# Balancing.net
KiCad netlist of a schematic drawn in Altium Designer
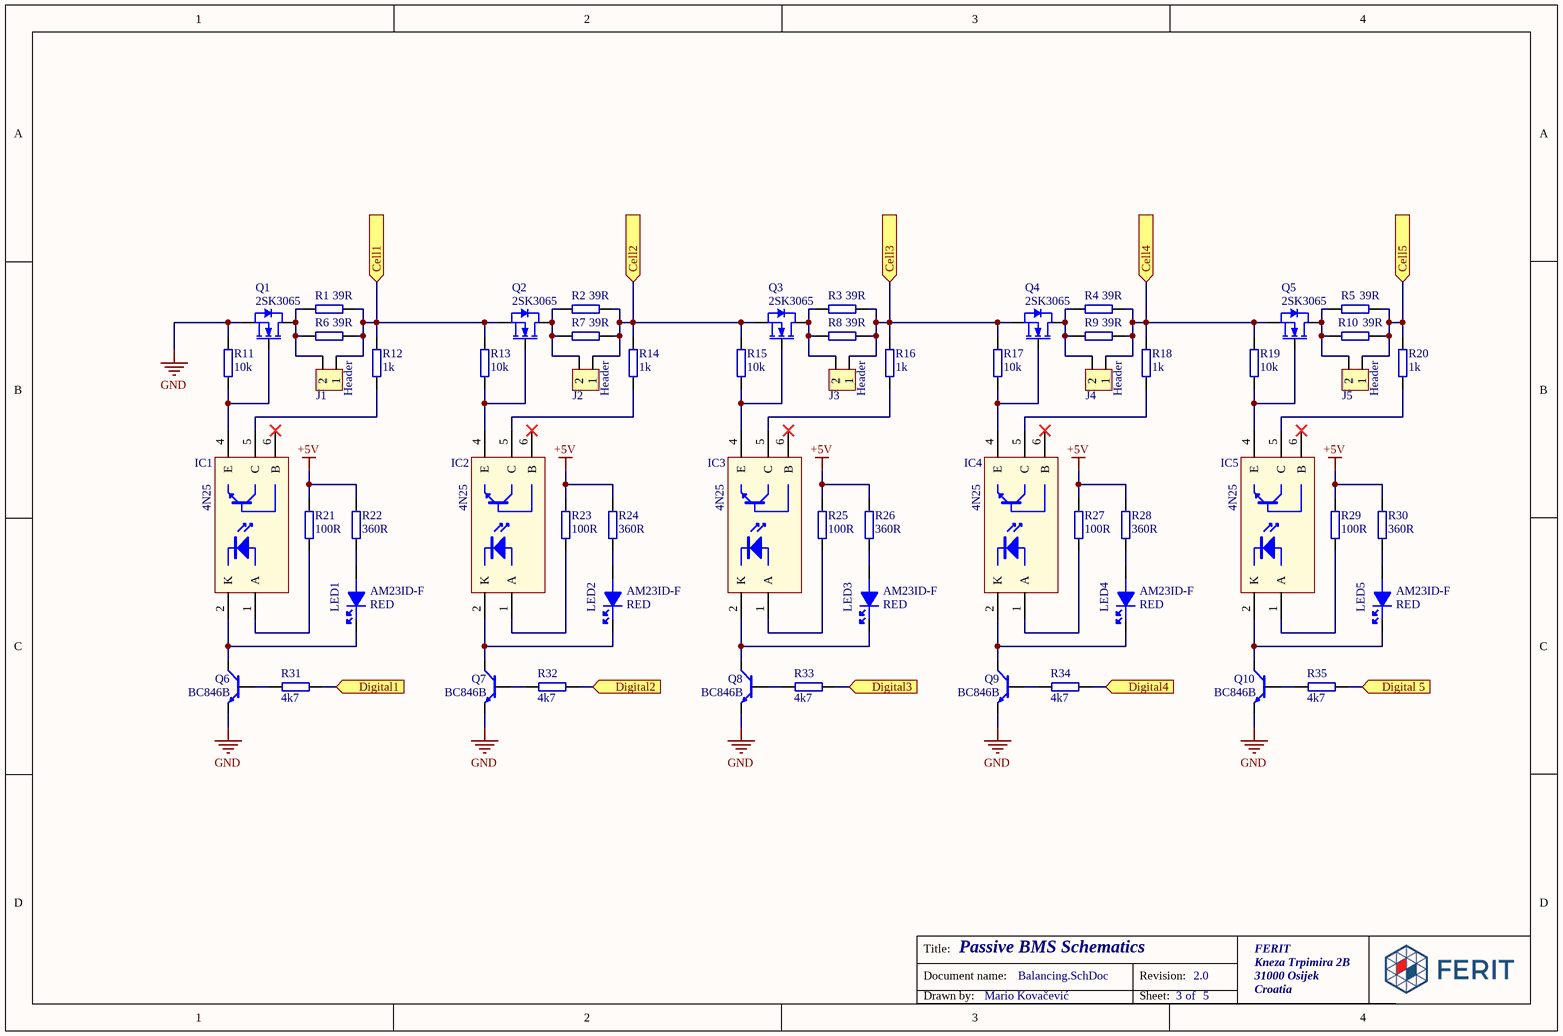
[diagram p0: Balancing.SchDoc]

(export (version "E")
  (design (tool "Eeschema 10.0.6"))
  (components
    (comp (ref "IC1")
      (value "4N25_DIP6")
      (footprint "DIP6")
      (description "Optocoupler [TH]")
      (fields
        (field (name "MANUFACTURER") "Vishay Semiconductors")
        (field (name "MANUFACTURER PART NUMBER") "4N25")
      )
      (libsource (lib "PassiveBMS_schlib") (part "4N25_DIP6"))
    )
    (comp (ref "IC2")
      (value "4N25_DIP6")
      (footprint "DIP6")
      (description "Optocoupler [TH]")
      (fields
        (field (name "MANUFACTURER") "Vishay Semiconductors")
        (field (name "MANUFACTURER PART NUMBER") "4N25")
      )
      (libsource (lib "PassiveBMS_schlib") (part "4N25_DIP6"))
    )
    (comp (ref "IC3")
      (value "4N25_DIP6")
      (footprint "DIP6")
      (description "Optocoupler [TH]")
      (fields
        (field (name "MANUFACTURER") "Vishay Semiconductors")
        (field (name "MANUFACTURER PART NUMBER") "4N25")
      )
      (libsource (lib "PassiveBMS_schlib") (part "4N25_DIP6"))
    )
    (comp (ref "IC4")
      (value "4N25_DIP6")
      (footprint "DIP6")
      (description "Optocoupler [TH]")
      (fields
        (field (name "MANUFACTURER") "Vishay Semiconductors")
        (field (name "MANUFACTURER PART NUMBER") "4N25")
      )
      (libsource (lib "PassiveBMS_schlib") (part "4N25_DIP6"))
    )
    (comp (ref "IC5")
      (value "4N25_DIP6")
      (footprint "DIP6")
      (description "Optocoupler [TH]")
      (fields
        (field (name "MANUFACTURER") "Vishay Semiconductors")
        (field (name "MANUFACTURER PART NUMBER") "4N25")
      )
      (libsource (lib "PassiveBMS_schlib") (part "4N25_DIP6"))
    )
    (comp (ref "J1")
      (value "2.54mm pitch")
      (footprint "HDR_1x2_2.54mm-MALE")
      (description "Header, 2-Pin [TH]")
      (fields
        (field (name "MANUFACTURER") "Molex")
        (field (name "MANUFACTURER PART NUMBER") "22-28-4150")
        (field (name "NAME") "Header")
        (field (name "PUBLISHER") "Altium Limited")
      )
      (libsource (lib "PassiveBMS_schlib") (part "Header 1x2"))
    )
    (comp (ref "J2")
      (value "2.54mm pitch")
      (footprint "HDR_1x2_2.54mm-MALE")
      (description "Header, 2-Pin [TH]")
      (fields
        (field (name "MANUFACTURER") "Molex")
        (field (name "MANUFACTURER PART NUMBER") "22-28-4150")
        (field (name "NAME") "Header")
        (field (name "PUBLISHER") "Altium Limited")
      )
      (libsource (lib "PassiveBMS_schlib") (part "Header 1x2"))
    )
    (comp (ref "J3")
      (value "2.54mm pitch")
      (footprint "HDR_1x2_2.54mm-MALE")
      (description "Header, 2-Pin [TH]")
      (fields
        (field (name "MANUFACTURER") "Molex")
        (field (name "MANUFACTURER PART NUMBER") "22-28-4150")
        (field (name "NAME") "Header")
        (field (name "PUBLISHER") "Altium Limited")
      )
      (libsource (lib "PassiveBMS_schlib") (part "Header 1x2"))
    )
    (comp (ref "J4")
      (value "2.54mm pitch")
      (footprint "HDR_1x2_2.54mm-MALE")
      (description "Header, 2-Pin [TH]")
      (fields
        (field (name "MANUFACTURER") "Molex")
        (field (name "MANUFACTURER PART NUMBER") "22-28-4150")
        (field (name "NAME") "Header")
        (field (name "PUBLISHER") "Altium Limited")
      )
      (libsource (lib "PassiveBMS_schlib") (part "Header 1x2"))
    )
    (comp (ref "J5")
      (value "2.54mm pitch")
      (footprint "HDR_1x2_2.54mm-MALE")
      (description "Header, 2-Pin [TH]")
      (fields
        (field (name "MANUFACTURER") "Molex")
        (field (name "MANUFACTURER PART NUMBER") "22-28-4150")
        (field (name "NAME") "Header")
        (field (name "PUBLISHER") "Altium Limited")
      )
      (libsource (lib "PassiveBMS_schlib") (part "Header 1x2"))
    )
    (comp (ref "LED1")
      (value "LED_SOT23")
      (footprint "LED_SOT23")
      (description "Red LED [SMD]")
      (fields
        (field (name "NAME") "RED")
        (field (name "MANUFACTURER") "Kingbright")
        (field (name "MANUFACTURER PART NUMBER") "AM23ID-F")
      )
      (libsource (lib "PassiveBMS_schlib") (part "LED_SOT23"))
    )
    (comp (ref "LED2")
      (value "LED_SOT23")
      (footprint "LED_SOT23")
      (description "Red LED [SMD]")
      (fields
        (field (name "NAME") "RED")
        (field (name "MANUFACTURER") "Kingbright")
        (field (name "MANUFACTURER PART NUMBER") "AM23ID-F")
      )
      (libsource (lib "PassiveBMS_schlib") (part "LED_SOT23"))
    )
    (comp (ref "LED3")
      (value "LED_SOT23")
      (footprint "LED_SOT23")
      (description "Red LED [SMD]")
      (fields
        (field (name "NAME") "RED")
        (field (name "MANUFACTURER") "Kingbright")
        (field (name "MANUFACTURER PART NUMBER") "AM23ID-F")
      )
      (libsource (lib "PassiveBMS_schlib") (part "LED_SOT23"))
    )
    (comp (ref "LED4")
      (value "LED_SOT23")
      (footprint "LED_SOT23")
      (description "Red LED [SMD]")
      (fields
        (field (name "NAME") "RED")
        (field (name "MANUFACTURER") "Kingbright")
        (field (name "MANUFACTURER PART NUMBER") "AM23ID-F")
      )
      (libsource (lib "PassiveBMS_schlib") (part "LED_SOT23"))
    )
    (comp (ref "LED5")
      (value "LED_SOT23")
      (footprint "LED_SOT23")
      (description "Red LED [SMD]")
      (fields
        (field (name "NAME") "RED")
        (field (name "MANUFACTURER") "Kingbright")
        (field (name "MANUFACTURER PART NUMBER") "AM23ID-F")
      )
      (libsource (lib "PassiveBMS_schlib") (part "LED_SOT23"))
    )
    (comp (ref "Q1")
      (value "2SK3065_SOT89")
      (footprint "N_MOSFET")
      (description "N Channel MOSFET [SMD]")
      (fields
        (field (name "MANUFACTURER_PART_NUMBER") "2SK3065T100")
        (field (name "NAME") "2SK3065")
        (field (name "MANUFACTURER") "Rohm")
        (field (name "COPYRIGHT") "Copyright (C) 2018 Accelerated Designs. All rights reserved")
      )
      (libsource (lib "PassiveBMS_schlib") (part "2SK3065_SOT89"))
    )
    (comp (ref "Q2")
      (value "2SK3065_SOT89")
      (footprint "N_MOSFET")
      (description "N Channel MOSFET [SMD]")
      (fields
        (field (name "MANUFACTURER_PART_NUMBER") "2SK3065T100")
        (field (name "NAME") "2SK3065")
        (field (name "MANUFACTURER") "Rohm")
        (field (name "COPYRIGHT") "Copyright (C) 2018 Accelerated Designs. All rights reserved")
      )
      (libsource (lib "PassiveBMS_schlib") (part "2SK3065_SOT89"))
    )
    (comp (ref "Q3")
      (value "2SK3065_SOT89")
      (footprint "N_MOSFET")
      (description "N Channel MOSFET [SMD]")
      (fields
        (field (name "MANUFACTURER_PART_NUMBER") "2SK3065T100")
        (field (name "NAME") "2SK3065")
        (field (name "MANUFACTURER") "Rohm")
        (field (name "COPYRIGHT") "Copyright (C) 2018 Accelerated Designs. All rights reserved")
      )
      (libsource (lib "PassiveBMS_schlib") (part "2SK3065_SOT89"))
    )
    (comp (ref "Q4")
      (value "2SK3065_SOT89")
      (footprint "N_MOSFET")
      (description "N Channel MOSFET [SMD]")
      (fields
        (field (name "MANUFACTURER_PART_NUMBER") "2SK3065T100")
        (field (name "NAME") "2SK3065")
        (field (name "MANUFACTURER") "Rohm")
        (field (name "COPYRIGHT") "Copyright (C) 2018 Accelerated Designs. All rights reserved")
      )
      (libsource (lib "PassiveBMS_schlib") (part "2SK3065_SOT89"))
    )
    (comp (ref "Q5")
      (value "2SK3065_SOT89")
      (footprint "N_MOSFET")
      (description "N Channel MOSFET [SMD]")
      (fields
        (field (name "MANUFACTURER_PART_NUMBER") "2SK3065T100")
        (field (name "NAME") "2SK3065")
        (field (name "MANUFACTURER") "Rohm")
        (field (name "COPYRIGHT") "Copyright (C) 2018 Accelerated Designs. All rights reserved")
      )
      (libsource (lib "PassiveBMS_schlib") (part "2SK3065_SOT89"))
    )
    (comp (ref "Q6")
      (value "BC846B_SOT23")
      (footprint "NPN_BJT_SOT23")
      (description "NPN transistor [SMD]")
      (fields
        (field (name "NAME") "BC846B")
        (field (name "MANUFACTURER PART NUMBER") "BC846ALT1G")
        (field (name "MANUFACTURER") "ON Semiconductor")
      )
      (libsource (lib "PassiveBMS_schlib") (part "BC846B_SOT23"))
    )
    (comp (ref "Q7")
      (value "BC846B_SOT23")
      (footprint "NPN_BJT_SOT23")
      (description "NPN transistor [SMD]")
      (fields
        (field (name "NAME") "BC846B")
        (field (name "MANUFACTURER PART NUMBER") "BC846ALT1G")
        (field (name "MANUFACTURER") "ON Semiconductor")
      )
      (libsource (lib "PassiveBMS_schlib") (part "BC846B_SOT23"))
    )
    (comp (ref "Q8")
      (value "BC846B_SOT23")
      (footprint "NPN_BJT_SOT23")
      (description "NPN transistor [SMD]")
      (fields
        (field (name "NAME") "BC846B")
        (field (name "MANUFACTURER PART NUMBER") "BC846ALT1G")
        (field (name "MANUFACTURER") "ON Semiconductor")
      )
      (libsource (lib "PassiveBMS_schlib") (part "BC846B_SOT23"))
    )
    (comp (ref "Q9")
      (value "BC846B_SOT23")
      (footprint "NPN_BJT_SOT23")
      (description "NPN transistor [SMD]")
      (fields
        (field (name "NAME") "BC846B")
        (field (name "MANUFACTURER PART NUMBER") "BC846ALT1G")
        (field (name "MANUFACTURER") "ON Semiconductor")
      )
      (libsource (lib "PassiveBMS_schlib") (part "BC846B_SOT23"))
    )
    (comp (ref "Q10")
      (value "BC846B_SOT23")
      (footprint "NPN_BJT_SOT23")
      (description "NPN transistor [SMD]")
      (fields
        (field (name "NAME") "BC846B")
        (field (name "MANUFACTURER PART NUMBER") "BC846ALT1G")
        (field (name "MANUFACTURER") "ON Semiconductor")
      )
      (libsource (lib "PassiveBMS_schlib") (part "BC846B_SOT23"))
    )
    (comp (ref "R1")
      (value "39R_2W")
      (footprint "R_2512")
      (description "Resistor [SMD]")
      (fields
        (field (name "NAME") "39R")
        (field (name "TOLERANCE") "1%")
        (field (name "MANUFACTURER") "TE Connectivity")
      )
      (libsource (lib "PassiveBMS_schlib") (part "R_39R_2512"))
    )
    (comp (ref "R2")
      (value "39R_2W")
      (footprint "R_2512")
      (description "Resistor [SMD]")
      (fields
        (field (name "NAME") "39R")
        (field (name "TOLERANCE") "1%")
        (field (name "MANUFACTURER") "TE Connectivity")
      )
      (libsource (lib "PassiveBMS_schlib") (part "R_39R_2512"))
    )
    (comp (ref "R3")
      (value "39R_2W")
      (footprint "R_2512")
      (description "Resistor [SMD]")
      (fields
        (field (name "NAME") "39R")
        (field (name "TOLERANCE") "1%")
        (field (name "MANUFACTURER") "TE Connectivity")
      )
      (libsource (lib "PassiveBMS_schlib") (part "R_39R_2512"))
    )
    (comp (ref "R4")
      (value "39R_2W")
      (footprint "R_2512")
      (description "Resistor [SMD]")
      (fields
        (field (name "NAME") "39R")
        (field (name "TOLERANCE") "1%")
        (field (name "MANUFACTURER") "TE Connectivity")
      )
      (libsource (lib "PassiveBMS_schlib") (part "R_39R_2512"))
    )
    (comp (ref "R5")
      (value "39R_2W")
      (footprint "R_2512")
      (description "Resistor [SMD]")
      (fields
        (field (name "NAME") "39R")
        (field (name "TOLERANCE") "1%")
        (field (name "MANUFACTURER") "TE Connectivity")
      )
      (libsource (lib "PassiveBMS_schlib") (part "R_39R_2512"))
    )
    (comp (ref "R6")
      (value "39R_2W")
      (footprint "R_2512")
      (description "Resistor [SMD]")
      (fields
        (field (name "NAME") "39R")
        (field (name "TOLERANCE") "1%")
        (field (name "MANUFACTURER") "TE Connectivity")
      )
      (libsource (lib "PassiveBMS_schlib") (part "R_39R_2512"))
    )
    (comp (ref "R7")
      (value "39R_2W")
      (footprint "R_2512")
      (description "Resistor [SMD]")
      (fields
        (field (name "NAME") "39R")
        (field (name "TOLERANCE") "1%")
        (field (name "MANUFACTURER") "TE Connectivity")
      )
      (libsource (lib "PassiveBMS_schlib") (part "R_39R_2512"))
    )
    (comp (ref "R8")
      (value "39R_2W")
      (footprint "R_2512")
      (description "Resistor [SMD]")
      (fields
        (field (name "NAME") "39R")
        (field (name "TOLERANCE") "1%")
        (field (name "MANUFACTURER") "TE Connectivity")
      )
      (libsource (lib "PassiveBMS_schlib") (part "R_39R_2512"))
    )
    (comp (ref "R9")
      (value "39R_2W")
      (footprint "R_2512")
      (description "Resistor [SMD]")
      (fields
        (field (name "NAME") "39R")
        (field (name "TOLERANCE") "1%")
        (field (name "MANUFACTURER") "TE Connectivity")
      )
      (libsource (lib "PassiveBMS_schlib") (part "R_39R_2512"))
    )
    (comp (ref "R10")
      (value "39R_2W")
      (footprint "R_2512")
      (description "Resistor [SMD]")
      (fields
        (field (name "NAME") "39R")
        (field (name "TOLERANCE") "1%")
        (field (name "MANUFACTURER") "TE Connectivity")
      )
      (libsource (lib "PassiveBMS_schlib") (part "R_39R_2512"))
    )
    (comp (ref "R11")
      (value "10k_125mW")
      (footprint "R_0805")
      (description "Resistor [SMD]")
      (fields
        (field (name "NAME") "10k")
        (field (name "TOLERANCE") "1%")
        (field (name "MANUFACTURER") "Vishay")
      )
      (libsource (lib "PassiveBMS_schlib") (part "R_10k_0805"))
    )
    (comp (ref "R12")
      (value "1k_125mW")
      (footprint "R_0805")
      (description "Resistor [SMD]")
      (fields
        (field (name "NAME") "1k")
        (field (name "TOLERANCE") "1%")
        (field (name "MANUFACTURER") "Vishay")
      )
      (libsource (lib "PassiveBMS_schlib") (part "R_1k_0805"))
    )
    (comp (ref "R13")
      (value "10k_125mW")
      (footprint "R_0805")
      (description "Resistor [SMD]")
      (fields
        (field (name "NAME") "10k")
        (field (name "TOLERANCE") "1%")
        (field (name "MANUFACTURER") "Vishay")
      )
      (libsource (lib "PassiveBMS_schlib") (part "R_10k_0805"))
    )
    (comp (ref "R14")
      (value "1k_125mW")
      (footprint "R_0805")
      (description "Resistor [SMD]")
      (fields
        (field (name "NAME") "1k")
        (field (name "TOLERANCE") "1%")
        (field (name "MANUFACTURER") "Vishay")
      )
      (libsource (lib "PassiveBMS_schlib") (part "R_1k_0805"))
    )
    (comp (ref "R15")
      (value "10k_125mW")
      (footprint "R_0805")
      (description "Resistor [SMD]")
      (fields
        (field (name "NAME") "10k")
        (field (name "TOLERANCE") "1%")
        (field (name "MANUFACTURER") "Vishay")
      )
      (libsource (lib "PassiveBMS_schlib") (part "R_10k_0805"))
    )
    (comp (ref "R16")
      (value "1k_125mW")
      (footprint "R_0805")
      (description "Resistor [SMD]")
      (fields
        (field (name "NAME") "1k")
        (field (name "TOLERANCE") "1%")
        (field (name "MANUFACTURER") "Vishay")
      )
      (libsource (lib "PassiveBMS_schlib") (part "R_1k_0805"))
    )
    (comp (ref "R17")
      (value "10k_125mW")
      (footprint "R_0805")
      (description "Resistor [SMD]")
      (fields
        (field (name "NAME") "10k")
        (field (name "TOLERANCE") "1%")
        (field (name "MANUFACTURER") "Vishay")
      )
      (libsource (lib "PassiveBMS_schlib") (part "R_10k_0805"))
    )
    (comp (ref "R18")
      (value "1k_125mW")
      (footprint "R_0805")
      (description "Resistor [SMD]")
      (fields
        (field (name "NAME") "1k")
        (field (name "TOLERANCE") "1%")
        (field (name "MANUFACTURER") "Vishay")
      )
      (libsource (lib "PassiveBMS_schlib") (part "R_1k_0805"))
    )
    (comp (ref "R19")
      (value "10k_125mW")
      (footprint "R_0805")
      (description "Resistor [SMD]")
      (fields
        (field (name "NAME") "10k")
        (field (name "TOLERANCE") "1%")
        (field (name "MANUFACTURER") "Vishay")
      )
      (libsource (lib "PassiveBMS_schlib") (part "R_10k_0805"))
    )
    (comp (ref "R20")
      (value "1k_125mW")
      (footprint "R_0805")
      (description "Resistor [SMD]")
      (fields
        (field (name "NAME") "1k")
        (field (name "TOLERANCE") "1%")
        (field (name "MANUFACTURER") "Vishay")
      )
      (libsource (lib "PassiveBMS_schlib") (part "R_1k_0805"))
    )
    (comp (ref "R21")
      (value "100R_500mW")
      (footprint "R_0805")
      (description "Resistor [SMD]")
      (fields
        (field (name "NAME") "100R")
        (field (name "TOLERANCE") "1%")
        (field (name "MANUFACTURER") "Vishay Dale")
      )
      (libsource (lib "PassiveBMS_schlib") (part "R_100R_0805"))
    )
    (comp (ref "R22")
      (value "360R_125mW")
      (footprint "R_0805")
      (description "Resistor [SMD]")
      (fields
        (field (name "NAME") "360R")
        (field (name "TOLERANCE") "1%")
        (field (name "MANUFACTURER") "Vishay")
      )
      (libsource (lib "PassiveBMS_schlib") (part "R_360R_0805"))
    )
    (comp (ref "R23")
      (value "100R_500mW")
      (footprint "R_0805")
      (description "Resistor [SMD]")
      (fields
        (field (name "NAME") "100R")
        (field (name "TOLERANCE") "1%")
        (field (name "MANUFACTURER") "Vishay Dale")
      )
      (libsource (lib "PassiveBMS_schlib") (part "R_100R_0805"))
    )
    (comp (ref "R24")
      (value "360R_125mW")
      (footprint "R_0805")
      (description "Resistor [SMD]")
      (fields
        (field (name "NAME") "360R")
        (field (name "TOLERANCE") "1%")
        (field (name "MANUFACTURER") "Vishay")
      )
      (libsource (lib "PassiveBMS_schlib") (part "R_360R_0805"))
    )
    (comp (ref "R25")
      (value "100R_500mW")
      (footprint "R_0805")
      (description "Resistor [SMD]")
      (fields
        (field (name "NAME") "100R")
        (field (name "TOLERANCE") "1%")
        (field (name "MANUFACTURER") "Vishay Dale")
      )
      (libsource (lib "PassiveBMS_schlib") (part "R_100R_0805"))
    )
    (comp (ref "R26")
      (value "360R_125mW")
      (footprint "R_0805")
      (description "Resistor [SMD]")
      (fields
        (field (name "NAME") "360R")
        (field (name "TOLERANCE") "1%")
        (field (name "MANUFACTURER") "Vishay")
      )
      (libsource (lib "PassiveBMS_schlib") (part "R_360R_0805"))
    )
    (comp (ref "R27")
      (value "100R_500mW")
      (footprint "R_0805")
      (description "Resistor [SMD]")
      (fields
        (field (name "NAME") "100R")
        (field (name "TOLERANCE") "1%")
        (field (name "MANUFACTURER") "Vishay Dale")
      )
      (libsource (lib "PassiveBMS_schlib") (part "R_100R_0805"))
    )
    (comp (ref "R28")
      (value "360R_125mW")
      (footprint "R_0805")
      (description "Resistor [SMD]")
      (fields
        (field (name "NAME") "360R")
        (field (name "TOLERANCE") "1%")
        (field (name "MANUFACTURER") "Vishay")
      )
      (libsource (lib "PassiveBMS_schlib") (part "R_360R_0805"))
    )
    (comp (ref "R29")
      (value "100R_500mW")
      (footprint "R_0805")
      (description "Resistor [SMD]")
      (fields
        (field (name "NAME") "100R")
        (field (name "TOLERANCE") "1%")
        (field (name "MANUFACTURER") "Vishay Dale")
      )
      (libsource (lib "PassiveBMS_schlib") (part "R_100R_0805"))
    )
    (comp (ref "R30")
      (value "360R_125mW")
      (footprint "R_0805")
      (description "Resistor [SMD]")
      (fields
        (field (name "NAME") "360R")
        (field (name "TOLERANCE") "1%")
        (field (name "MANUFACTURER") "Vishay")
      )
      (libsource (lib "PassiveBMS_schlib") (part "R_360R_0805"))
    )
    (comp (ref "R31")
      (value "4k7_125mW")
      (footprint "R_0805")
      (description "Resistor [SMD]")
      (fields
        (field (name "NAME") "4k7")
        (field (name "TOLERANCE") "1%")
        (field (name "MANUFACTURER") "Vishay")
      )
      (libsource (lib "PassiveBMS_schlib") (part "R_4k7_0805"))
    )
    (comp (ref "R32")
      (value "4k7_125mW")
      (footprint "R_0805")
      (description "Resistor [SMD]")
      (fields
        (field (name "NAME") "4k7")
        (field (name "TOLERANCE") "1%")
        (field (name "MANUFACTURER") "Vishay")
      )
      (libsource (lib "PassiveBMS_schlib") (part "R_4k7_0805"))
    )
    (comp (ref "R33")
      (value "4k7_125mW")
      (footprint "R_0805")
      (description "Resistor [SMD]")
      (fields
        (field (name "NAME") "4k7")
        (field (name "TOLERANCE") "1%")
        (field (name "MANUFACTURER") "Vishay")
      )
      (libsource (lib "PassiveBMS_schlib") (part "R_4k7_0805"))
    )
    (comp (ref "R34")
      (value "4k7_125mW")
      (footprint "R_0805")
      (description "Resistor [SMD]")
      (fields
        (field (name "NAME") "4k7")
        (field (name "TOLERANCE") "1%")
        (field (name "MANUFACTURER") "Vishay")
      )
      (libsource (lib "PassiveBMS_schlib") (part "R_4k7_0805"))
    )
    (comp (ref "R35")
      (value "4k7_125mW")
      (footprint "R_0805")
      (description "Resistor [SMD]")
      (fields
        (field (name "NAME") "4k7")
        (field (name "TOLERANCE") "1%")
        (field (name "MANUFACTURER") "Vishay")
      )
      (libsource (lib "PassiveBMS_schlib") (part "R_4k7_0805"))
    )
  )
  (nets
    (net (code "1") (name "+5V") (class "Default")
      (node (ref "R21") (pin "2") (pinfunction "2_2") (pintype "passive"))
      (node (ref "R22") (pin "1") (pinfunction "1_1") (pintype "passive"))
      (node (ref "R23") (pin "1") (pinfunction "1_1") (pintype "passive"))
      (node (ref "R24") (pin "1") (pinfunction "1_1") (pintype "passive"))
      (node (ref "R25") (pin "1") (pinfunction "1_1") (pintype "passive"))
      (node (ref "R26") (pin "1") (pinfunction "1_1") (pintype "passive"))
      (node (ref "R27") (pin "1") (pinfunction "1_1") (pintype "passive"))
      (node (ref "R28") (pin "1") (pinfunction "1_1") (pintype "passive"))
      (node (ref "R29") (pin "1") (pinfunction "1_1") (pintype "passive"))
      (node (ref "R30") (pin "1") (pinfunction "1_1") (pintype "passive"))
    )
    (net (code "2") (name "/Cell1") (class "Default")
      (node (ref "J1") (pin "1") (pinfunction "1_1") (pintype "passive"))
      (node (ref "Q2") (pin "3") (pinfunction "S_3") (pintype "passive"))
      (node (ref "R1") (pin "1") (pinfunction "1_1") (pintype "passive"))
      (node (ref "R12") (pin "1") (pinfunction "1_1") (pintype "passive"))
      (node (ref "R13") (pin "1") (pinfunction "1_1") (pintype "passive"))
      (node (ref "R6") (pin "1") (pinfunction "1_1") (pintype "passive"))
    )
    (net (code "3") (name "/Cell2") (class "Default")
      (node (ref "J2") (pin "1") (pinfunction "1_1") (pintype "passive"))
      (node (ref "Q3") (pin "3") (pinfunction "S_3") (pintype "passive"))
      (node (ref "R14") (pin "1") (pinfunction "1_1") (pintype "passive"))
      (node (ref "R15") (pin "1") (pinfunction "1_1") (pintype "passive"))
      (node (ref "R2") (pin "1") (pinfunction "1_1") (pintype "passive"))
      (node (ref "R7") (pin "1") (pinfunction "1_1") (pintype "passive"))
    )
    (net (code "4") (name "/Cell3") (class "Default")
      (node (ref "J3") (pin "1") (pinfunction "1_1") (pintype "passive"))
      (node (ref "Q4") (pin "3") (pinfunction "S_3") (pintype "passive"))
      (node (ref "R16") (pin "1") (pinfunction "1_1") (pintype "passive"))
      (node (ref "R17") (pin "1") (pinfunction "1_1") (pintype "passive"))
      (node (ref "R3") (pin "1") (pinfunction "1_1") (pintype "passive"))
      (node (ref "R8") (pin "1") (pinfunction "1_1") (pintype "passive"))
    )
    (net (code "5") (name "/Cell4") (class "Default")
      (node (ref "J4") (pin "1") (pinfunction "1_1") (pintype "passive"))
      (node (ref "Q5") (pin "3") (pinfunction "S_3") (pintype "passive"))
      (node (ref "R18") (pin "1") (pinfunction "1_1") (pintype "passive"))
      (node (ref "R19") (pin "1") (pinfunction "1_1") (pintype "passive"))
      (node (ref "R4") (pin "1") (pinfunction "1_1") (pintype "passive"))
      (node (ref "R9") (pin "1") (pinfunction "1_1") (pintype "passive"))
    )
    (net (code "6") (name "/Cell5") (class "Default")
      (node (ref "J5") (pin "1") (pinfunction "1_1") (pintype "passive"))
      (node (ref "R10") (pin "1") (pinfunction "1_1") (pintype "passive"))
      (node (ref "R20") (pin "1") (pinfunction "1_1") (pintype "passive"))
      (node (ref "R5") (pin "1") (pinfunction "1_1") (pintype "passive"))
    )
    (net (code "7") (name "/Digital 5") (class "Default")
      (node (ref "R35") (pin "2") (pinfunction "2_2") (pintype "passive"))
    )
    (net (code "8") (name "/Digital1") (class "Default")
      (node (ref "R31") (pin "1") (pinfunction "1_1") (pintype "passive"))
    )
    (net (code "9") (name "/Digital2") (class "Default")
      (node (ref "R32") (pin "1") (pinfunction "1_1") (pintype "passive"))
    )
    (net (code "10") (name "/Digital3") (class "Default")
      (node (ref "R33") (pin "2") (pinfunction "2_2") (pintype "passive"))
    )
    (net (code "11") (name "/Digital4") (class "Default")
      (node (ref "R34") (pin "1") (pinfunction "1_1") (pintype "passive"))
    )
    (net (code "12") (name "GND") (class "Default")
      (node (ref "Q1") (pin "3") (pinfunction "S_3") (pintype "passive"))
      (node (ref "Q10") (pin "3") (pinfunction "E_3") (pintype "passive"))
      (node (ref "Q6") (pin "3") (pinfunction "E_3") (pintype "passive"))
      (node (ref "Q7") (pin "3") (pinfunction "E_3") (pintype "passive"))
      (node (ref "Q8") (pin "3") (pinfunction "E_3") (pintype "passive"))
      (node (ref "Q9") (pin "3") (pinfunction "E_3") (pintype "passive"))
      (node (ref "R11") (pin "1") (pinfunction "1_1") (pintype "passive"))
    )
    (net (code "13") (name "Net-(IC1-A)") (class "Default")
      (node (ref "IC1") (pin "1") (pinfunction "A_1") (pintype "passive"))
      (node (ref "R21") (pin "1") (pinfunction "1_1") (pintype "passive"))
    )
    (net (code "14") (name "Net-(IC1-C)") (class "Default")
      (node (ref "IC1") (pin "5") (pinfunction "C_5") (pintype "passive"))
      (node (ref "R12") (pin "2") (pinfunction "2_2") (pintype "passive"))
    )
    (net (code "15") (name "Net-(IC1-E)") (class "Default")
      (node (ref "IC1") (pin "4") (pinfunction "E_4") (pintype "passive"))
      (node (ref "Q1") (pin "1") (pinfunction "G_1") (pintype "passive"))
      (node (ref "R11") (pin "2") (pinfunction "2_2") (pintype "passive"))
    )
    (net (code "16") (name "Net-(IC1-K)") (class "Default")
      (node (ref "IC1") (pin "2") (pinfunction "K_2") (pintype "passive"))
      (node (ref "LED1") (pin "3") (pinfunction "K_3") (pintype "passive"))
      (node (ref "Q6") (pin "1") (pinfunction "C_1") (pintype "passive"))
    )
    (net (code "17") (name "Net-(IC2-A)") (class "Default")
      (node (ref "IC2") (pin "1") (pinfunction "A_1") (pintype "passive"))
      (node (ref "R23") (pin "2") (pinfunction "2_2") (pintype "passive"))
    )
    (net (code "18") (name "Net-(IC2-C)") (class "Default")
      (node (ref "IC2") (pin "5") (pinfunction "C_5") (pintype "passive"))
      (node (ref "R14") (pin "2") (pinfunction "2_2") (pintype "passive"))
    )
    (net (code "19") (name "Net-(IC2-E)") (class "Default")
      (node (ref "IC2") (pin "4") (pinfunction "E_4") (pintype "passive"))
      (node (ref "Q2") (pin "1") (pinfunction "G_1") (pintype "passive"))
      (node (ref "R13") (pin "2") (pinfunction "2_2") (pintype "passive"))
    )
    (net (code "20") (name "Net-(IC2-K)") (class "Default")
      (node (ref "IC2") (pin "2") (pinfunction "K_2") (pintype "passive"))
      (node (ref "LED2") (pin "3") (pinfunction "K_3") (pintype "passive"))
      (node (ref "Q7") (pin "1") (pinfunction "C_1") (pintype "passive"))
    )
    (net (code "21") (name "Net-(IC3-A)") (class "Default")
      (node (ref "IC3") (pin "1") (pinfunction "A_1") (pintype "passive"))
      (node (ref "R25") (pin "2") (pinfunction "2_2") (pintype "passive"))
    )
    (net (code "22") (name "Net-(IC3-C)") (class "Default")
      (node (ref "IC3") (pin "5") (pinfunction "C_5") (pintype "passive"))
      (node (ref "R16") (pin "2") (pinfunction "2_2") (pintype "passive"))
    )
    (net (code "23") (name "Net-(IC3-E)") (class "Default")
      (node (ref "IC3") (pin "4") (pinfunction "E_4") (pintype "passive"))
      (node (ref "Q3") (pin "1") (pinfunction "G_1") (pintype "passive"))
      (node (ref "R15") (pin "2") (pinfunction "2_2") (pintype "passive"))
    )
    (net (code "24") (name "Net-(IC3-K)") (class "Default")
      (node (ref "IC3") (pin "2") (pinfunction "K_2") (pintype "passive"))
      (node (ref "LED3") (pin "3") (pinfunction "K_3") (pintype "passive"))
      (node (ref "Q8") (pin "1") (pinfunction "C_1") (pintype "passive"))
    )
    (net (code "25") (name "Net-(IC4-A)") (class "Default")
      (node (ref "IC4") (pin "1") (pinfunction "A_1") (pintype "passive"))
      (node (ref "R27") (pin "2") (pinfunction "2_2") (pintype "passive"))
    )
    (net (code "26") (name "Net-(IC4-C)") (class "Default")
      (node (ref "IC4") (pin "5") (pinfunction "C_5") (pintype "passive"))
      (node (ref "R18") (pin "2") (pinfunction "2_2") (pintype "passive"))
    )
    (net (code "27") (name "Net-(IC4-E)") (class "Default")
      (node (ref "IC4") (pin "4") (pinfunction "E_4") (pintype "passive"))
      (node (ref "Q4") (pin "1") (pinfunction "G_1") (pintype "passive"))
      (node (ref "R17") (pin "2") (pinfunction "2_2") (pintype "passive"))
    )
    (net (code "28") (name "Net-(IC4-K)") (class "Default")
      (node (ref "IC4") (pin "2") (pinfunction "K_2") (pintype "passive"))
      (node (ref "LED4") (pin "3") (pinfunction "K_3") (pintype "passive"))
      (node (ref "Q9") (pin "1") (pinfunction "C_1") (pintype "passive"))
    )
    (net (code "29") (name "Net-(IC5-A)") (class "Default")
      (node (ref "IC5") (pin "1") (pinfunction "A_1") (pintype "passive"))
      (node (ref "R29") (pin "2") (pinfunction "2_2") (pintype "passive"))
    )
    (net (code "30") (name "Net-(IC5-C)") (class "Default")
      (node (ref "IC5") (pin "5") (pinfunction "C_5") (pintype "passive"))
      (node (ref "R20") (pin "2") (pinfunction "2_2") (pintype "passive"))
    )
    (net (code "31") (name "Net-(IC5-E)") (class "Default")
      (node (ref "IC5") (pin "4") (pinfunction "E_4") (pintype "passive"))
      (node (ref "Q5") (pin "1") (pinfunction "G_1") (pintype "passive"))
      (node (ref "R19") (pin "2") (pinfunction "2_2") (pintype "passive"))
    )
    (net (code "32") (name "Net-(IC5-K)") (class "Default")
      (node (ref "IC5") (pin "2") (pinfunction "K_2") (pintype "passive"))
      (node (ref "LED5") (pin "3") (pinfunction "K_3") (pintype "passive"))
      (node (ref "Q10") (pin "1") (pinfunction "C_1") (pintype "passive"))
    )
    (net (code "33") (name "Net-(LED1-A)") (class "Default")
      (node (ref "LED1") (pin "1") (pinfunction "A_1") (pintype "passive"))
      (node (ref "R22") (pin "2") (pinfunction "2_2") (pintype "passive"))
    )
    (net (code "34") (name "Net-(LED2-A)") (class "Default")
      (node (ref "LED2") (pin "1") (pinfunction "A_1") (pintype "passive"))
      (node (ref "R24") (pin "2") (pinfunction "2_2") (pintype "passive"))
    )
    (net (code "35") (name "Net-(LED3-A)") (class "Default")
      (node (ref "LED3") (pin "1") (pinfunction "A_1") (pintype "passive"))
      (node (ref "R26") (pin "2") (pinfunction "2_2") (pintype "passive"))
    )
    (net (code "36") (name "Net-(LED4-A)") (class "Default")
      (node (ref "LED4") (pin "1") (pinfunction "A_1") (pintype "passive"))
      (node (ref "R28") (pin "2") (pinfunction "2_2") (pintype "passive"))
    )
    (net (code "37") (name "Net-(LED5-A)") (class "Default")
      (node (ref "LED5") (pin "1") (pinfunction "A_1") (pintype "passive"))
      (node (ref "R30") (pin "2") (pinfunction "2_2") (pintype "passive"))
    )
    (net (code "38") (name "Net-(Q1-D)") (class "Default")
      (node (ref "J1") (pin "2") (pinfunction "2_2") (pintype "passive"))
      (node (ref "Q1") (pin "2") (pinfunction "D_2") (pintype "passive"))
      (node (ref "R1") (pin "2") (pinfunction "2_2") (pintype "passive"))
      (node (ref "R6") (pin "2") (pinfunction "2_2") (pintype "passive"))
    )
    (net (code "39") (name "Net-(Q2-D)") (class "Default")
      (node (ref "J2") (pin "2") (pinfunction "2_2") (pintype "passive"))
      (node (ref "Q2") (pin "2") (pinfunction "D_2") (pintype "passive"))
      (node (ref "R2") (pin "2") (pinfunction "2_2") (pintype "passive"))
      (node (ref "R7") (pin "2") (pinfunction "2_2") (pintype "passive"))
    )
    (net (code "40") (name "Net-(Q3-D)") (class "Default")
      (node (ref "J3") (pin "2") (pinfunction "2_2") (pintype "passive"))
      (node (ref "Q3") (pin "2") (pinfunction "D_2") (pintype "passive"))
      (node (ref "R3") (pin "2") (pinfunction "2_2") (pintype "passive"))
      (node (ref "R8") (pin "2") (pinfunction "2_2") (pintype "passive"))
    )
    (net (code "41") (name "Net-(Q4-D)") (class "Default")
      (node (ref "J4") (pin "2") (pinfunction "2_2") (pintype "passive"))
      (node (ref "Q4") (pin "2") (pinfunction "D_2") (pintype "passive"))
      (node (ref "R4") (pin "2") (pinfunction "2_2") (pintype "passive"))
      (node (ref "R9") (pin "2") (pinfunction "2_2") (pintype "passive"))
    )
    (net (code "42") (name "Net-(Q5-D)") (class "Default")
      (node (ref "J5") (pin "2") (pinfunction "2_2") (pintype "passive"))
      (node (ref "Q5") (pin "2") (pinfunction "D_2") (pintype "passive"))
      (node (ref "R10") (pin "2") (pinfunction "2_2") (pintype "passive"))
      (node (ref "R5") (pin "2") (pinfunction "2_2") (pintype "passive"))
    )
    (net (code "43") (name "Net-(Q6-B)") (class "Default")
      (node (ref "Q6") (pin "2") (pinfunction "B_2") (pintype "passive"))
      (node (ref "R31") (pin "2") (pinfunction "2_2") (pintype "passive"))
    )
    (net (code "44") (name "Net-(Q7-B)") (class "Default")
      (node (ref "Q7") (pin "2") (pinfunction "B_2") (pintype "passive"))
      (node (ref "R32") (pin "2") (pinfunction "2_2") (pintype "passive"))
    )
    (net (code "45") (name "Net-(Q8-B)") (class "Default")
      (node (ref "Q8") (pin "2") (pinfunction "B_2") (pintype "passive"))
      (node (ref "R33") (pin "1") (pinfunction "1_1") (pintype "passive"))
    )
    (net (code "46") (name "Net-(Q9-B)") (class "Default")
      (node (ref "Q9") (pin "2") (pinfunction "B_2") (pintype "passive"))
      (node (ref "R34") (pin "2") (pinfunction "2_2") (pintype "passive"))
    )
    (net (code "47") (name "Net-(Q10-B)") (class "Default")
      (node (ref "Q10") (pin "2") (pinfunction "B_2") (pintype "passive"))
      (node (ref "R35") (pin "1") (pinfunction "1_1") (pintype "passive"))
    )
    (net (code "48") (name "unconnected-(IC1-B-Pad6)") (class "Default")
      (node (ref "IC1") (pin "6") (pinfunction "B_6") (pintype "passive+no_connect"))
    )
    (net (code "49") (name "unconnected-(IC2-B-Pad6)") (class "Default")
      (node (ref "IC2") (pin "6") (pinfunction "B_6") (pintype "passive+no_connect"))
    )
    (net (code "50") (name "unconnected-(IC3-B-Pad6)") (class "Default")
      (node (ref "IC3") (pin "6") (pinfunction "B_6") (pintype "passive+no_connect"))
    )
    (net (code "51") (name "unconnected-(IC4-B-Pad6)") (class "Default")
      (node (ref "IC4") (pin "6") (pinfunction "B_6") (pintype "passive+no_connect"))
    )
    (net (code "52") (name "unconnected-(IC5-B-Pad6)") (class "Default")
      (node (ref "IC5") (pin "6") (pinfunction "B_6") (pintype "passive+no_connect"))
    )
  )
)
